# 9-LCD.net
KiCad netlist of a schematic drawn in Altium Designer
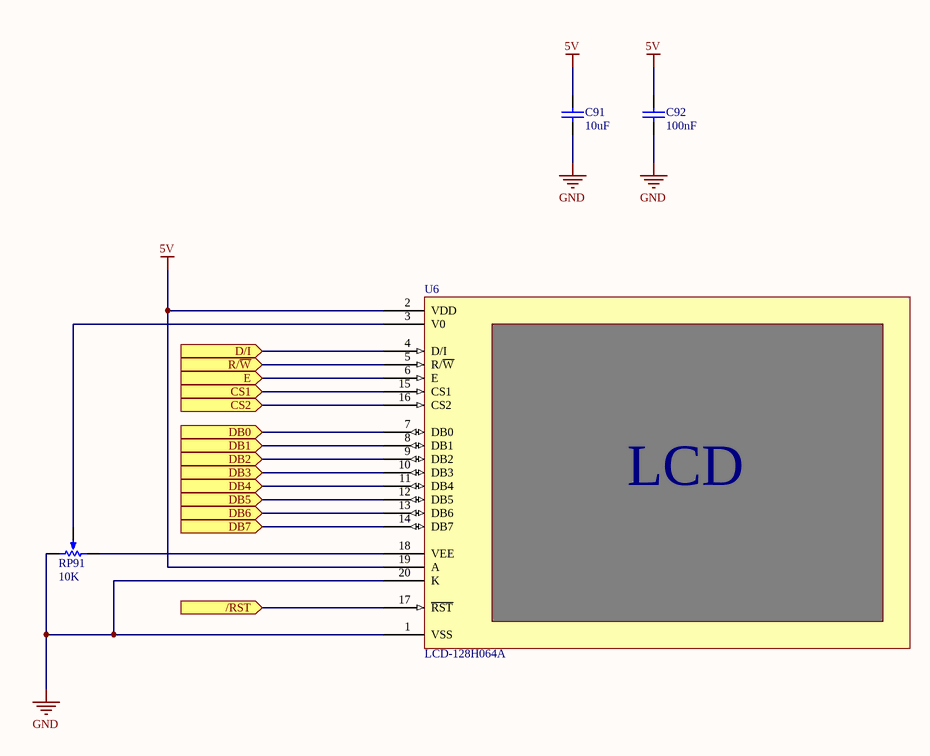
[diagram p0: 9-LCD.SchDoc]

(export (version "E")
  (design (tool "Eeschema 10.0.6"))
  (components
    (comp (ref "C91")
      (value "10uF")
      (footprint "capa 1206")
      (description "Capacitor")
      (libsource (lib "Miscellaneous Devices") (part "Cap"))
    )
    (comp (ref "C92")
      (value "100nF")
      (footprint "capa 1206")
      (description "Capacitor")
      (libsource (lib "Miscellaneous Devices") (part "Cap"))
    )
    (comp (ref "RP91")
      (value "10K")
      (footprint "3313J-1")
      (description "Potentiometer")
      (libsource (lib "Miscellaneous Devices") (part "RPot"))
    )
    (comp (ref "U6")
      (value "LCD-128H064A")
      (footprint "LCD-128H064A")
      (libsource (lib "0x2a002a") (part "LCD-128H064A"))
    )
  )
  (nets
    (net (code "1") (name "/CS1") (class "Default")
      (node (ref "U6") (pin "15") (pinfunction "CS1_15") (pintype "input"))
    )
    (net (code "2") (name "/CS2") (class "Default")
      (node (ref "U6") (pin "16") (pinfunction "CS2_16") (pintype "input"))
    )
    (net (code "3") (name "/DB0") (class "Default")
      (node (ref "U6") (pin "7") (pinfunction "DB0_7") (pintype "bidirectional"))
    )
    (net (code "4") (name "/DB1") (class "Default")
      (node (ref "U6") (pin "8") (pinfunction "DB1_8") (pintype "bidirectional"))
    )
    (net (code "5") (name "/DB2") (class "Default")
      (node (ref "U6") (pin "9") (pinfunction "DB2_9") (pintype "bidirectional"))
    )
    (net (code "6") (name "/DB3") (class "Default")
      (node (ref "U6") (pin "10") (pinfunction "DB3_10") (pintype "bidirectional"))
    )
    (net (code "7") (name "/DB4") (class "Default")
      (node (ref "U6") (pin "11") (pinfunction "DB4_11") (pintype "bidirectional"))
    )
    (net (code "8") (name "/DB5") (class "Default")
      (node (ref "U6") (pin "12") (pinfunction "DB5_12") (pintype "bidirectional"))
    )
    (net (code "9") (name "/DB6") (class "Default")
      (node (ref "U6") (pin "13") (pinfunction "DB6_13") (pintype "bidirectional"))
    )
    (net (code "10") (name "/DB7") (class "Default")
      (node (ref "U6") (pin "14") (pinfunction "DB7_14") (pintype "bidirectional"))
    )
    (net (code "11") (name "/D{slash}I") (class "Default")
      (node (ref "U6") (pin "4") (pinfunction "D/I_4") (pintype "input"))
    )
    (net (code "12") (name "/E") (class "Default")
      (node (ref "U6") (pin "6") (pinfunction "E_6") (pintype "input"))
    )
    (net (code "13") (name "/R{slash}~{W}") (class "Default")
      (node (ref "U6") (pin "5") (pinfunction "R/~{W}_5") (pintype "input"))
    )
    (net (code "14") (name "/{slash}RST") (class "Default")
      (node (ref "U6") (pin "17") (pinfunction "~{RST}_17") (pintype "input"))
    )
    (net (code "15") (name "5V") (class "Default")
      (node (ref "C91") (pin "1") (pinfunction "1_1") (pintype "passive"))
      (node (ref "C92") (pin "1") (pinfunction "1_1") (pintype "passive"))
      (node (ref "U6") (pin "19") (pinfunction "A_19") (pintype "power_in"))
      (node (ref "U6") (pin "2") (pinfunction "VDD_2") (pintype "power_in"))
    )
    (net (code "16") (name "GND") (class "Default")
      (node (ref "C91") (pin "2") (pinfunction "2_2") (pintype "passive"))
      (node (ref "C92") (pin "2") (pinfunction "2_2") (pintype "passive"))
      (node (ref "RP91") (pin "2") (pinfunction "BOT_2") (pintype "passive"))
      (node (ref "U6") (pin "1") (pinfunction "VSS_1") (pintype "power_in"))
      (node (ref "U6") (pin "20") (pinfunction "K_20") (pintype "power_in"))
    )
    (net (code "17") (name "Net-(RP91-TAP)") (class "Default")
      (node (ref "RP91") (pin "3") (pinfunction "TAP_3") (pintype "passive"))
      (node (ref "U6") (pin "3") (pinfunction "V0_3") (pintype "power_in"))
    )
    (net (code "18") (name "Net-(RP91-TOP)") (class "Default")
      (node (ref "RP91") (pin "1") (pinfunction "TOP_1") (pintype "passive"))
      (node (ref "U6") (pin "18") (pinfunction "VEE_18") (pintype "power_in"))
    )
  )
)
